# CONNECTOR_A.net
KiCad netlist of a schematic drawn in Altium Designer
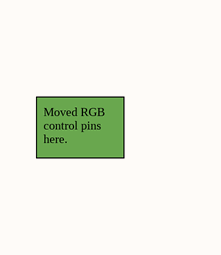
[diagram p0: CONNECTOR_A.SchDoc, left]
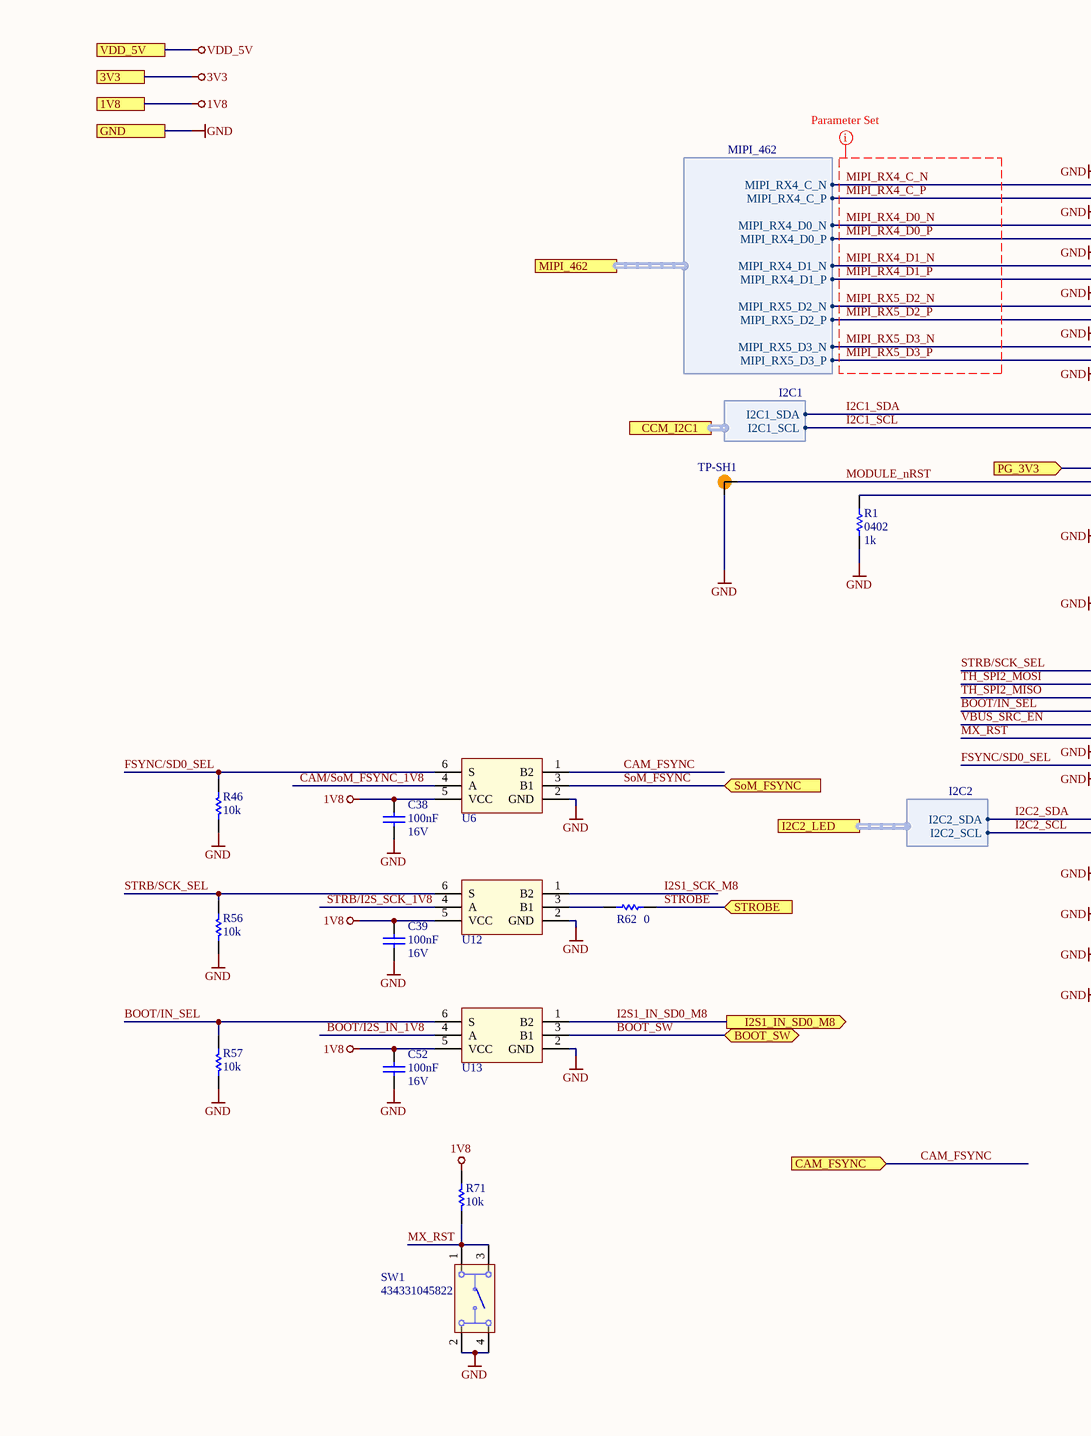
[diagram p1: CONNECTOR_A.SchDoc, middle]
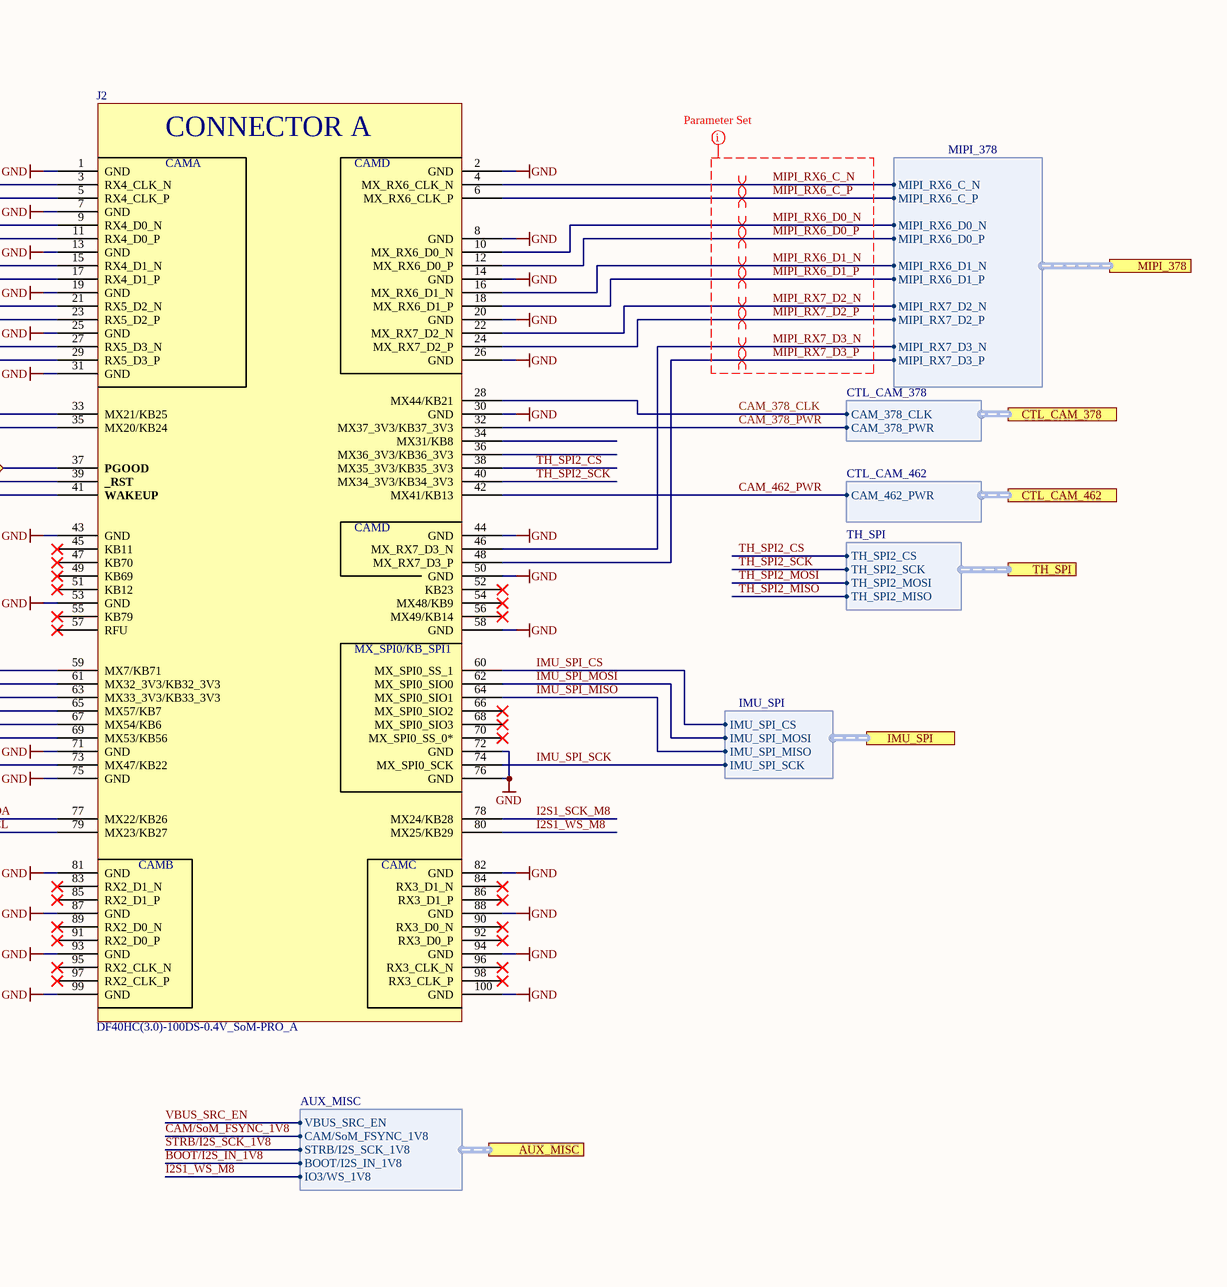
[diagram p2: CONNECTOR_A.SchDoc, right]

(export (version "E")
  (design (tool "Eeschema 10.0.6"))
  (components
    (comp (ref "C38")
      (value "100nF")
      (footprint "CAPC0402(1005)60_L")
      (description "CAP CER 0.1UF 16V X7R 0402 10%")
      (fields
        (field (name "VOLTAGE RATING") "16V")
        (field (name "TOLERANCE") "10%")
        (field (name "Comment") "CL05B104KO5NFNC")
      )
      (libsource (lib "Luxonis LLC") (part "GRM188R61C475KAAJD"))
    )
    (comp (ref "C39")
      (value "100nF")
      (footprint "CAPC0402(1005)60_L")
      (description "CAP CER 0.1UF 16V X7R 0402 10%")
      (fields
        (field (name "VOLTAGE RATING") "16V")
        (field (name "TOLERANCE") "10%")
        (field (name "Comment") "CL05B104KO5NFNC")
      )
      (libsource (lib "Luxonis LLC") (part "GRM188R61C475KAAJD"))
    )
    (comp (ref "C52")
      (value "100nF")
      (footprint "CAPC0402(1005)60_L")
      (description "CAP CER 0.1UF 16V X7R 0402 10%")
      (fields
        (field (name "VOLTAGE RATING") "16V")
        (field (name "TOLERANCE") "10%")
        (field (name "Comment") "CL05B104KO5NFNC")
      )
      (libsource (lib "Luxonis LLC") (part "GRM188R61C475KAAJD"))
    )
    (comp (ref "J2")
      (value "DF40HC(3.0)-100DS-0.4V_SoM-PRO_A")
      (footprint "CON_A_BW2099_SoM_DF40HC-3.0-100DS-0.4V_minpad")
      (description "OAK-SoM-Pro_S2/S3 base board conn. A")
      (libsource (lib "Luxonis LLC") (part "DF40HC(3.0)-100DS-0.4V_SoM-PRO_A"))
    )
    (comp (ref "R1")
      (value "1k")
      (footprint "RESC1005X40X25ML05T05")
      (description "RES SMD 1K OHM 1% 0.1W 0402")
      (fields
        (field (name "CASE/PACKAGE") "0402")
        (field (name "TOLERANCE") "1%")
        (field (name "Comment") "ERJ-2RKF1001X")
      )
      (libsource (lib "Luxonis LLC") (part "Default resistor symbol"))
    )
    (comp (ref "R46")
      (value "10k")
      (footprint "RESC0402(1005)_L")
      (description "RES SMD 10K OHM 1% 1/16W 0402")
      (fields (field (name "TOLERANCE") "1%") (field (name "Comment") "RC0402FR-1310KL"))
      (libsource (lib "Luxonis LLC") (part "RC0402FR-0722RL_1"))
    )
    (comp (ref "R56")
      (value "10k")
      (footprint "RESC0402(1005)_L")
      (description "RES SMD 10K OHM 1% 1/16W 0402")
      (fields (field (name "TOLERANCE") "1%") (field (name "Comment") "RC0402FR-1310KL"))
      (libsource (lib "Luxonis LLC") (part "RC0402FR-0722RL_1"))
    )
    (comp (ref "R57")
      (value "10k")
      (footprint "RESC0402(1005)_L")
      (description "RES SMD 10K OHM 1% 1/16W 0402")
      (fields (field (name "TOLERANCE") "1%") (field (name "Comment") "RC0402FR-1310KL"))
      (libsource (lib "Luxonis LLC") (part "RC0402FR-0722RL_1"))
    )
    (comp (ref "R62")
      (value "0")
      (footprint "RESC0402(1005)_L")
      (description "RES SMD 0 OHM 5% 1/16W 0402")
      (fields (field (name "TOLERANCE") "5%"))
      (libsource (lib "Luxonis LLC") (part "Default resistor symbol"))
    )
    (comp (ref "R71")
      (value "10k")
      (footprint "RESC0402(1005)_L")
      (description "RES SMD 10K OHM 1% 1/16W 0402")
      (fields (field (name "TOLERANCE") "1%") (field (name "Comment") "RC0402FR-1310KL"))
      (libsource (lib "Luxonis LLC") (part "RC0402FR-0722RL_1"))
    )
    (comp (ref "SW1")
      (value "434331045822")
      (footprint "434331045822")
      (libsource (lib "Luxonis LLC") (part "WE-TACT-SW-4"))
    )
    (comp (ref "TP-SH1")
      (value "TEST_SHORT")
      (footprint "TP_short")
      (libsource (lib "Luxonis LLC") (part "TEST_SHORT"))
    )
    (comp (ref "U6")
      (value "SN74LVC1G3157DCKR")
      (footprint "DCK6_65")
      (description "IC SWITCH SPDT SC70-6 1 Circuit IC Switch 2:1 15Ohm SC-70-6")
      (libsource (lib "Luxonis LLC") (part "SN74LVC1G3157DCKR"))
    )
    (comp (ref "U12")
      (value "SN74LVC1G3157DCKR")
      (footprint "DCK6_65")
      (description "IC SWITCH SPDT SC70-6 1 Circuit IC Switch 2:1 15Ohm SC-70-6")
      (libsource (lib "Luxonis LLC") (part "SN74LVC1G3157DCKR"))
    )
    (comp (ref "U13")
      (value "SN74LVC1G3157DCKR")
      (footprint "DCK6_65")
      (description "IC SWITCH SPDT SC70-6 1 Circuit IC Switch 2:1 15Ohm SC-70-6")
      (libsource (lib "Luxonis LLC") (part "SN74LVC1G3157DCKR"))
    )
  )
  (nets
    (net (code "10") (name "/BOOT_SW") (class "Default")
      (node (ref "U13") (pin "3") (pinfunction "B1_3") (pintype "passive"))
    )
    (net (code "11") (name "/BOOT{slash}I2S_IN_1V8") (class "Default")
      (node (ref "U13") (pin "4") (pinfunction "A_4") (pintype "passive"))
    )
    (net (code "12") (name "/BOOT{slash}IN_SEL") (class "Default")
      (node (ref "J2") (pin "65") (pinfunction "MX57/KB7_65") (pintype "passive"))
      (node (ref "R57") (pin "2") (pinfunction "2_2") (pintype "passive"))
      (node (ref "U13") (pin "6") (pinfunction "S_6") (pintype "passive"))
    )
    (net (code "13") (name "/CAM_378_CLK") (class "Default")
      (node (ref "J2") (pin "28") (pinfunction "MX44/KB21_28") (pintype "passive"))
    )
    (net (code "14") (name "/CAM_378_PWR") (class "Default")
      (node (ref "J2") (pin "32") (pinfunction "MX37_3V3/KB37_3V3_32") (pintype "passive"))
    )
    (net (code "15") (name "/CAM_462_PWR") (class "Default")
      (node (ref "J2") (pin "42") (pinfunction "MX41/KB13_42") (pintype "passive"))
    )
    (net (code "16") (name "/CAM_FSYNC") (class "Default")
      (node (ref "U6") (pin "1") (pinfunction "B2_1") (pintype "passive"))
    )
    (net (code "17") (name "/CAM{slash}SoM_FSYNC_1V8") (class "Default")
      (node (ref "U6") (pin "4") (pinfunction "A_4") (pintype "passive"))
    )
    (net (code "18") (name "/FSYNC{slash}SD0_SEL") (class "Default")
      (node (ref "J2") (pin "73") (pinfunction "MX47/KB22_73") (pintype "passive"))
      (node (ref "R46") (pin "2") (pinfunction "2_2") (pintype "passive"))
      (node (ref "U6") (pin "6") (pinfunction "S_6") (pintype "passive"))
    )
    (net (code "19") (name "/I2C1_SCL") (class "Default")
      (node (ref "J2") (pin "35") (pinfunction "MX20/KB24_35") (pintype "passive"))
    )
    (net (code "20") (name "/I2C1_SDA") (class "Default")
      (node (ref "J2") (pin "33") (pinfunction "MX21/KB25_33") (pintype "passive"))
    )
    (net (code "21") (name "/I2C2_SCL") (class "Default")
      (node (ref "J2") (pin "79") (pinfunction "MX23/KB27_79") (pintype "passive"))
    )
    (net (code "22") (name "/I2C2_SDA") (class "Default")
      (node (ref "J2") (pin "77") (pinfunction "MX22/KB26_77") (pintype "passive"))
    )
    (net (code "23") (name "/I2S1_IN_SD0_M8") (class "Default")
      (node (ref "U13") (pin "1") (pinfunction "B2_1") (pintype "passive"))
    )
    (net (code "24") (name "/I2S1_SCK_M8") (class "Default")
      (node (ref "J2") (pin "78") (pinfunction "MX24/KB28_78") (pintype "passive"))
      (node (ref "U12") (pin "1") (pinfunction "B2_1") (pintype "passive"))
    )
    (net (code "25") (name "/I2S1_WS_M8") (class "Default")
      (node (ref "J2") (pin "80") (pinfunction "MX25/KB29_80") (pintype "passive"))
    )
    (net (code "26") (name "/IMU_SPI_CS") (class "Default")
      (node (ref "J2") (pin "60") (pinfunction "MX_SPI0_SS_1_60") (pintype "passive"))
    )
    (net (code "27") (name "/IMU_SPI_MISO") (class "Default")
      (node (ref "J2") (pin "64") (pinfunction "MX_SPI0_SIO1_64") (pintype "passive"))
    )
    (net (code "28") (name "/IMU_SPI_MOSI") (class "Default")
      (node (ref "J2") (pin "62") (pinfunction "MX_SPI0_SIO0_62") (pintype "passive"))
    )
    (net (code "29") (name "/IMU_SPI_SCK") (class "Default")
      (node (ref "J2") (pin "74") (pinfunction "MX_SPI0_SCK_74") (pintype "passive"))
    )
    (net (code "30") (name "/MIPI_RX4_C_N") (class "Default")
      (node (ref "J2") (pin "3") (pinfunction "RX4_CLK_N_3") (pintype "passive"))
    )
    (net (code "31") (name "/MIPI_RX4_C_P") (class "Default")
      (node (ref "J2") (pin "5") (pinfunction "RX4_CLK_P_5") (pintype "passive"))
    )
    (net (code "32") (name "/MIPI_RX4_D0_N") (class "Default")
      (node (ref "J2") (pin "9") (pinfunction "RX4_D0_N_9") (pintype "passive"))
    )
    (net (code "33") (name "/MIPI_RX4_D0_P") (class "Default")
      (node (ref "J2") (pin "11") (pinfunction "RX4_D0_P_11") (pintype "passive"))
    )
    (net (code "34") (name "/MIPI_RX4_D1_N") (class "Default")
      (node (ref "J2") (pin "15") (pinfunction "RX4_D1_N_15") (pintype "passive"))
    )
    (net (code "35") (name "/MIPI_RX4_D1_P") (class "Default")
      (node (ref "J2") (pin "17") (pinfunction "RX4_D1_P_17") (pintype "passive"))
    )
    (net (code "36") (name "/MIPI_RX5_D2_N") (class "Default")
      (node (ref "J2") (pin "21") (pinfunction "RX5_D2_N_21") (pintype "passive"))
    )
    (net (code "37") (name "/MIPI_RX5_D2_P") (class "Default")
      (node (ref "J2") (pin "23") (pinfunction "RX5_D2_P_23") (pintype "passive"))
    )
    (net (code "38") (name "/MIPI_RX5_D3_N") (class "Default")
      (node (ref "J2") (pin "27") (pinfunction "RX5_D3_N_27") (pintype "passive"))
    )
    (net (code "39") (name "/MIPI_RX5_D3_P") (class "Default")
      (node (ref "J2") (pin "29") (pinfunction "RX5_D3_P_29") (pintype "passive"))
    )
    (net (code "40") (name "/MIPI_RX6_C_N") (class "Default")
      (node (ref "J2") (pin "4") (pinfunction "MX_RX6_CLK_N_4") (pintype "passive"))
    )
    (net (code "41") (name "/MIPI_RX6_C_P") (class "Default")
      (node (ref "J2") (pin "6") (pinfunction "MX_RX6_CLK_P_6") (pintype "passive"))
    )
    (net (code "42") (name "/MIPI_RX6_D0_N") (class "Default")
      (node (ref "J2") (pin "10") (pinfunction "MX_RX6_D0_N_10") (pintype "passive"))
    )
    (net (code "43") (name "/MIPI_RX6_D0_P") (class "Default")
      (node (ref "J2") (pin "12") (pinfunction "MX_RX6_D0_P_12") (pintype "passive"))
    )
    (net (code "44") (name "/MIPI_RX6_D1_N") (class "Default")
      (node (ref "J2") (pin "16") (pinfunction "MX_RX6_D1_N_16") (pintype "passive"))
    )
    (net (code "45") (name "/MIPI_RX6_D1_P") (class "Default")
      (node (ref "J2") (pin "18") (pinfunction "MX_RX6_D1_P_18") (pintype "passive"))
    )
    (net (code "46") (name "/MIPI_RX7_D2_N") (class "Default")
      (node (ref "J2") (pin "22") (pinfunction "MX_RX7_D2_N_22") (pintype "passive"))
    )
    (net (code "47") (name "/MIPI_RX7_D2_P") (class "Default")
      (node (ref "J2") (pin "24") (pinfunction "MX_RX7_D2_P_24") (pintype "passive"))
    )
    (net (code "48") (name "/MIPI_RX7_D3_N") (class "Default")
      (node (ref "J2") (pin "46") (pinfunction "MX_RX7_D3_N_46") (pintype "passive"))
    )
    (net (code "49") (name "/MIPI_RX7_D3_P") (class "Default")
      (node (ref "J2") (pin "48") (pinfunction "MX_RX7_D3_P_48") (pintype "passive"))
    )
    (net (code "50") (name "/MODULE_nRST") (class "Default")
      (node (ref "J2") (pin "39") (pinfunction "_RST_39") (pintype "passive"))
      (node (ref "TP-SH1") (pin "2") (pintype "passive"))
    )
    (net (code "51") (name "/MX_RST") (class "Default")
      (node (ref "J2") (pin "69") (pinfunction "MX53/KB56_69") (pintype "passive"))
      (node (ref "R71") (pin "1") (pinfunction "1_1") (pintype "passive"))
      (node (ref "SW1") (pin "1") (pinfunction "1_1") (pintype "passive"))
      (node (ref "SW1") (pin "3") (pinfunction "3_3") (pintype "passive"))
    )
    (net (code "52") (name "/PG_3V3") (class "Default")
      (node (ref "J2") (pin "37") (pinfunction "PGOOD_37") (pintype "passive"))
    )
    (net (code "53") (name "/STRB{slash}I2S_SCK_1V8") (class "Default")
      (node (ref "U12") (pin "4") (pinfunction "A_4") (pintype "passive"))
    )
    (net (code "54") (name "/STRB{slash}SCK_SEL") (class "Default")
      (node (ref "J2") (pin "59") (pinfunction "MX7/KB71_59") (pintype "passive"))
      (node (ref "R56") (pin "2") (pinfunction "2_2") (pintype "passive"))
      (node (ref "U12") (pin "6") (pinfunction "S_6") (pintype "passive"))
    )
    (net (code "55") (name "/STROBE") (class "Default")
      (node (ref "R62") (pin "1") (pinfunction "1_1") (pintype "passive"))
    )
    (net (code "56") (name "/SoM_FSYNC") (class "Default")
      (node (ref "U6") (pin "3") (pinfunction "B1_3") (pintype "passive"))
    )
    (net (code "57") (name "/TH_SPI2_CS") (class "Default")
      (node (ref "J2") (pin "38") (pinfunction "MX35_3V3/KB35_3V3_38") (pintype "passive"))
    )
    (net (code "58") (name "/TH_SPI2_MISO") (class "Default")
      (node (ref "J2") (pin "63") (pinfunction "MX33_3V3/KB33_3V3_63") (pintype "passive"))
    )
    (net (code "59") (name "/TH_SPI2_MOSI") (class "Default")
      (node (ref "J2") (pin "61") (pinfunction "MX32_3V3/KB32_3V3_61") (pintype "passive"))
    )
    (net (code "60") (name "/TH_SPI2_SCK") (class "Default")
      (node (ref "J2") (pin "40") (pinfunction "MX34_3V3/KB34_3V3_40") (pintype "passive"))
    )
    (net (code "61") (name "/VBUS_SRC_EN") (class "Default")
      (node (ref "J2") (pin "67") (pinfunction "MX54/KB6_67") (pintype "passive"))
    )
    (net (code "71") (name "1V8") (class "Default")
      (node (ref "C38") (pin "2") (pinfunction "2_2") (pintype "passive"))
      (node (ref "C39") (pin "2") (pinfunction "2_2") (pintype "passive"))
      (node (ref "C52") (pin "2") (pinfunction "2_2") (pintype "passive"))
      (node (ref "R71") (pin "2") (pinfunction "2_2") (pintype "passive"))
      (node (ref "U12") (pin "5") (pinfunction "VCC_5") (pintype "passive"))
      (node (ref "U13") (pin "5") (pinfunction "VCC_5") (pintype "passive"))
      (node (ref "U6") (pin "5") (pinfunction "VCC_5") (pintype "passive"))
    )
    (net (code "73") (name "GND") (class "Default")
      (node (ref "C38") (pin "1") (pinfunction "1_1") (pintype "passive"))
      (node (ref "C39") (pin "1") (pinfunction "1_1") (pintype "passive"))
      (node (ref "C52") (pin "1") (pinfunction "1_1") (pintype "passive"))
      (node (ref "J2") (pin "1") (pinfunction "GND_1") (pintype "passive"))
      (node (ref "J2") (pin "100") (pinfunction "GND_100") (pintype "passive"))
      (node (ref "J2") (pin "13") (pinfunction "GND_13") (pintype "passive"))
      (node (ref "J2") (pin "14") (pinfunction "GND_14") (pintype "passive"))
      (node (ref "J2") (pin "19") (pinfunction "GND_19") (pintype "passive"))
      (node (ref "J2") (pin "2") (pinfunction "GND_2") (pintype "passive"))
      (node (ref "J2") (pin "20") (pinfunction "GND_20") (pintype "passive"))
      (node (ref "J2") (pin "25") (pinfunction "GND_25") (pintype "passive"))
      (node (ref "J2") (pin "26") (pinfunction "GND_26") (pintype "passive"))
      (node (ref "J2") (pin "30") (pinfunction "GND_30") (pintype "passive"))
      (node (ref "J2") (pin "31") (pinfunction "GND_31") (pintype "passive"))
      (node (ref "J2") (pin "43") (pinfunction "GND_43") (pintype "passive"))
      (node (ref "J2") (pin "44") (pinfunction "GND_44") (pintype "passive"))
      (node (ref "J2") (pin "50") (pinfunction "GND_50") (pintype "passive"))
      (node (ref "J2") (pin "53") (pinfunction "GND_53") (pintype "passive"))
      (node (ref "J2") (pin "58") (pinfunction "GND_58") (pintype "passive"))
      (node (ref "J2") (pin "7") (pinfunction "GND_7") (pintype "passive"))
      (node (ref "J2") (pin "71") (pinfunction "GND_71") (pintype "passive"))
      (node (ref "J2") (pin "72") (pinfunction "GND_72") (pintype "passive"))
      (node (ref "J2") (pin "75") (pinfunction "GND_75") (pintype "passive"))
      (node (ref "J2") (pin "76") (pinfunction "GND_76") (pintype "passive"))
      (node (ref "J2") (pin "8") (pinfunction "GND_8") (pintype "passive"))
      (node (ref "J2") (pin "81") (pinfunction "GND_81") (pintype "passive"))
      (node (ref "J2") (pin "82") (pinfunction "GND_82") (pintype "passive"))
      (node (ref "J2") (pin "87") (pinfunction "GND_87") (pintype "passive"))
      (node (ref "J2") (pin "88") (pinfunction "GND_88") (pintype "passive"))
      (node (ref "J2") (pin "93") (pinfunction "GND_93") (pintype "passive"))
      (node (ref "J2") (pin "94") (pinfunction "GND_94") (pintype "passive"))
      (node (ref "J2") (pin "99") (pinfunction "GND_99") (pintype "passive"))
      (node (ref "R1") (pin "1") (pinfunction "1_1") (pintype "passive"))
      (node (ref "R46") (pin "1") (pinfunction "1_1") (pintype "passive"))
      (node (ref "R56") (pin "1") (pinfunction "1_1") (pintype "passive"))
      (node (ref "R57") (pin "1") (pinfunction "1_1") (pintype "passive"))
      (node (ref "SW1") (pin "2") (pinfunction "2_2") (pintype "passive"))
      (node (ref "SW1") (pin "4") (pinfunction "4_4") (pintype "passive"))
      (node (ref "TP-SH1") (pin "1") (pintype "passive"))
      (node (ref "U12") (pin "2") (pinfunction "GND_2") (pintype "passive"))
      (node (ref "U13") (pin "2") (pinfunction "GND_2") (pintype "passive"))
      (node (ref "U6") (pin "2") (pinfunction "GND_2") (pintype "passive"))
    )
    (net (code "74") (name "Net-(J2-WAKEUP)") (class "Default")
      (node (ref "J2") (pin "41") (pinfunction "WAKEUP_41") (pintype "passive"))
      (node (ref "R1") (pin "2") (pinfunction "2_2") (pintype "passive"))
    )
    (net (code "75") (name "Net-(U12-B1)") (class "Default")
      (node (ref "R62") (pin "2") (pinfunction "2_2") (pintype "passive"))
      (node (ref "U12") (pin "3") (pinfunction "B1_3") (pintype "passive"))
    )
    (net (code "77") (name "unconnected-(J2-KB11-Pad45)") (class "Default")
      (node (ref "J2") (pin "45") (pinfunction "KB11_45") (pintype "passive+no_connect"))
    )
    (net (code "78") (name "unconnected-(J2-KB12-Pad51)") (class "Default")
      (node (ref "J2") (pin "51") (pinfunction "KB12_51") (pintype "passive+no_connect"))
    )
    (net (code "79") (name "unconnected-(J2-KB23-Pad52)") (class "Default")
      (node (ref "J2") (pin "52") (pinfunction "KB23_52") (pintype "passive+no_connect"))
    )
    (net (code "80") (name "unconnected-(J2-KB69-Pad49)") (class "Default")
      (node (ref "J2") (pin "49") (pinfunction "KB69_49") (pintype "passive+no_connect"))
    )
    (net (code "81") (name "unconnected-(J2-KB70-Pad47)") (class "Default")
      (node (ref "J2") (pin "47") (pinfunction "KB70_47") (pintype "passive+no_connect"))
    )
    (net (code "82") (name "unconnected-(J2-KB79-Pad55)") (class "Default")
      (node (ref "J2") (pin "55") (pinfunction "KB79_55") (pintype "passive+no_connect"))
    )
    (net (code "83") (name "unconnected-(J2-MX31{slash}KB8-Pad34)") (class "Default")
      (node (ref "J2") (pin "34") (pinfunction "MX31/KB8_34") (pintype "passive"))
    )
    (net (code "84") (name "unconnected-(J2-MX36_3V3{slash}KB36_3V3-Pad36)") (class "Default")
      (node (ref "J2") (pin "36") (pinfunction "MX36_3V3/KB36_3V3_36") (pintype "passive"))
    )
    (net (code "85") (name "unconnected-(J2-MX48{slash}KB9-Pad54)") (class "Default")
      (node (ref "J2") (pin "54") (pinfunction "MX48/KB9_54") (pintype "passive+no_connect"))
    )
    (net (code "86") (name "unconnected-(J2-MX49{slash}KB14-Pad56)") (class "Default")
      (node (ref "J2") (pin "56") (pinfunction "MX49/KB14_56") (pintype "passive+no_connect"))
    )
    (net (code "87") (name "unconnected-(J2-MX_SPI0_SIO2-Pad66)") (class "Default")
      (node (ref "J2") (pin "66") (pinfunction "MX_SPI0_SIO2_66") (pintype "passive+no_connect"))
    )
    (net (code "88") (name "unconnected-(J2-MX_SPI0_SIO3-Pad68)") (class "Default")
      (node (ref "J2") (pin "68") (pinfunction "MX_SPI0_SIO3_68") (pintype "passive+no_connect"))
    )
    (net (code "89") (name "unconnected-(J2-MX_SPI0_SS_0*-Pad70)") (class "Default")
      (node (ref "J2") (pin "70") (pinfunction "MX_SPI0_SS_0*_70") (pintype "passive+no_connect"))
    )
    (net (code "90") (name "unconnected-(J2-RFU-Pad57)") (class "Default")
      (node (ref "J2") (pin "57") (pinfunction "RFU_57") (pintype "passive+no_connect"))
    )
    (net (code "91") (name "unconnected-(J2-RX2_CLK_N-Pad95)") (class "Default")
      (node (ref "J2") (pin "95") (pinfunction "RX2_CLK_N_95") (pintype "passive+no_connect"))
    )
    (net (code "92") (name "unconnected-(J2-RX2_CLK_P-Pad97)") (class "Default")
      (node (ref "J2") (pin "97") (pinfunction "RX2_CLK_P_97") (pintype "passive+no_connect"))
    )
    (net (code "93") (name "unconnected-(J2-RX2_D0_N-Pad89)") (class "Default")
      (node (ref "J2") (pin "89") (pinfunction "RX2_D0_N_89") (pintype "passive+no_connect"))
    )
    (net (code "94") (name "unconnected-(J2-RX2_D0_P-Pad91)") (class "Default")
      (node (ref "J2") (pin "91") (pinfunction "RX2_D0_P_91") (pintype "passive+no_connect"))
    )
    (net (code "95") (name "unconnected-(J2-RX2_D1_N-Pad83)") (class "Default")
      (node (ref "J2") (pin "83") (pinfunction "RX2_D1_N_83") (pintype "passive+no_connect"))
    )
    (net (code "96") (name "unconnected-(J2-RX2_D1_P-Pad85)") (class "Default")
      (node (ref "J2") (pin "85") (pinfunction "RX2_D1_P_85") (pintype "passive+no_connect"))
    )
    (net (code "97") (name "unconnected-(J2-RX3_CLK_N-Pad96)") (class "Default")
      (node (ref "J2") (pin "96") (pinfunction "RX3_CLK_N_96") (pintype "passive+no_connect"))
    )
    (net (code "98") (name "unconnected-(J2-RX3_CLK_P-Pad98)") (class "Default")
      (node (ref "J2") (pin "98") (pinfunction "RX3_CLK_P_98") (pintype "passive+no_connect"))
    )
    (net (code "99") (name "unconnected-(J2-RX3_D0_N-Pad90)") (class "Default")
      (node (ref "J2") (pin "90") (pinfunction "RX3_D0_N_90") (pintype "passive+no_connect"))
    )
    (net (code "100") (name "unconnected-(J2-RX3_D0_P-Pad92)") (class "Default")
      (node (ref "J2") (pin "92") (pinfunction "RX3_D0_P_92") (pintype "passive+no_connect"))
    )
    (net (code "101") (name "unconnected-(J2-RX3_D1_N-Pad84)") (class "Default")
      (node (ref "J2") (pin "84") (pinfunction "RX3_D1_N_84") (pintype "passive+no_connect"))
    )
    (net (code "102") (name "unconnected-(J2-RX3_D1_P-Pad86)") (class "Default")
      (node (ref "J2") (pin "86") (pinfunction "RX3_D1_P_86") (pintype "passive+no_connect"))
    )
  )
)
